# STM32G431C6T6.net
KiCad netlist of a schematic drawn in Altium Designer
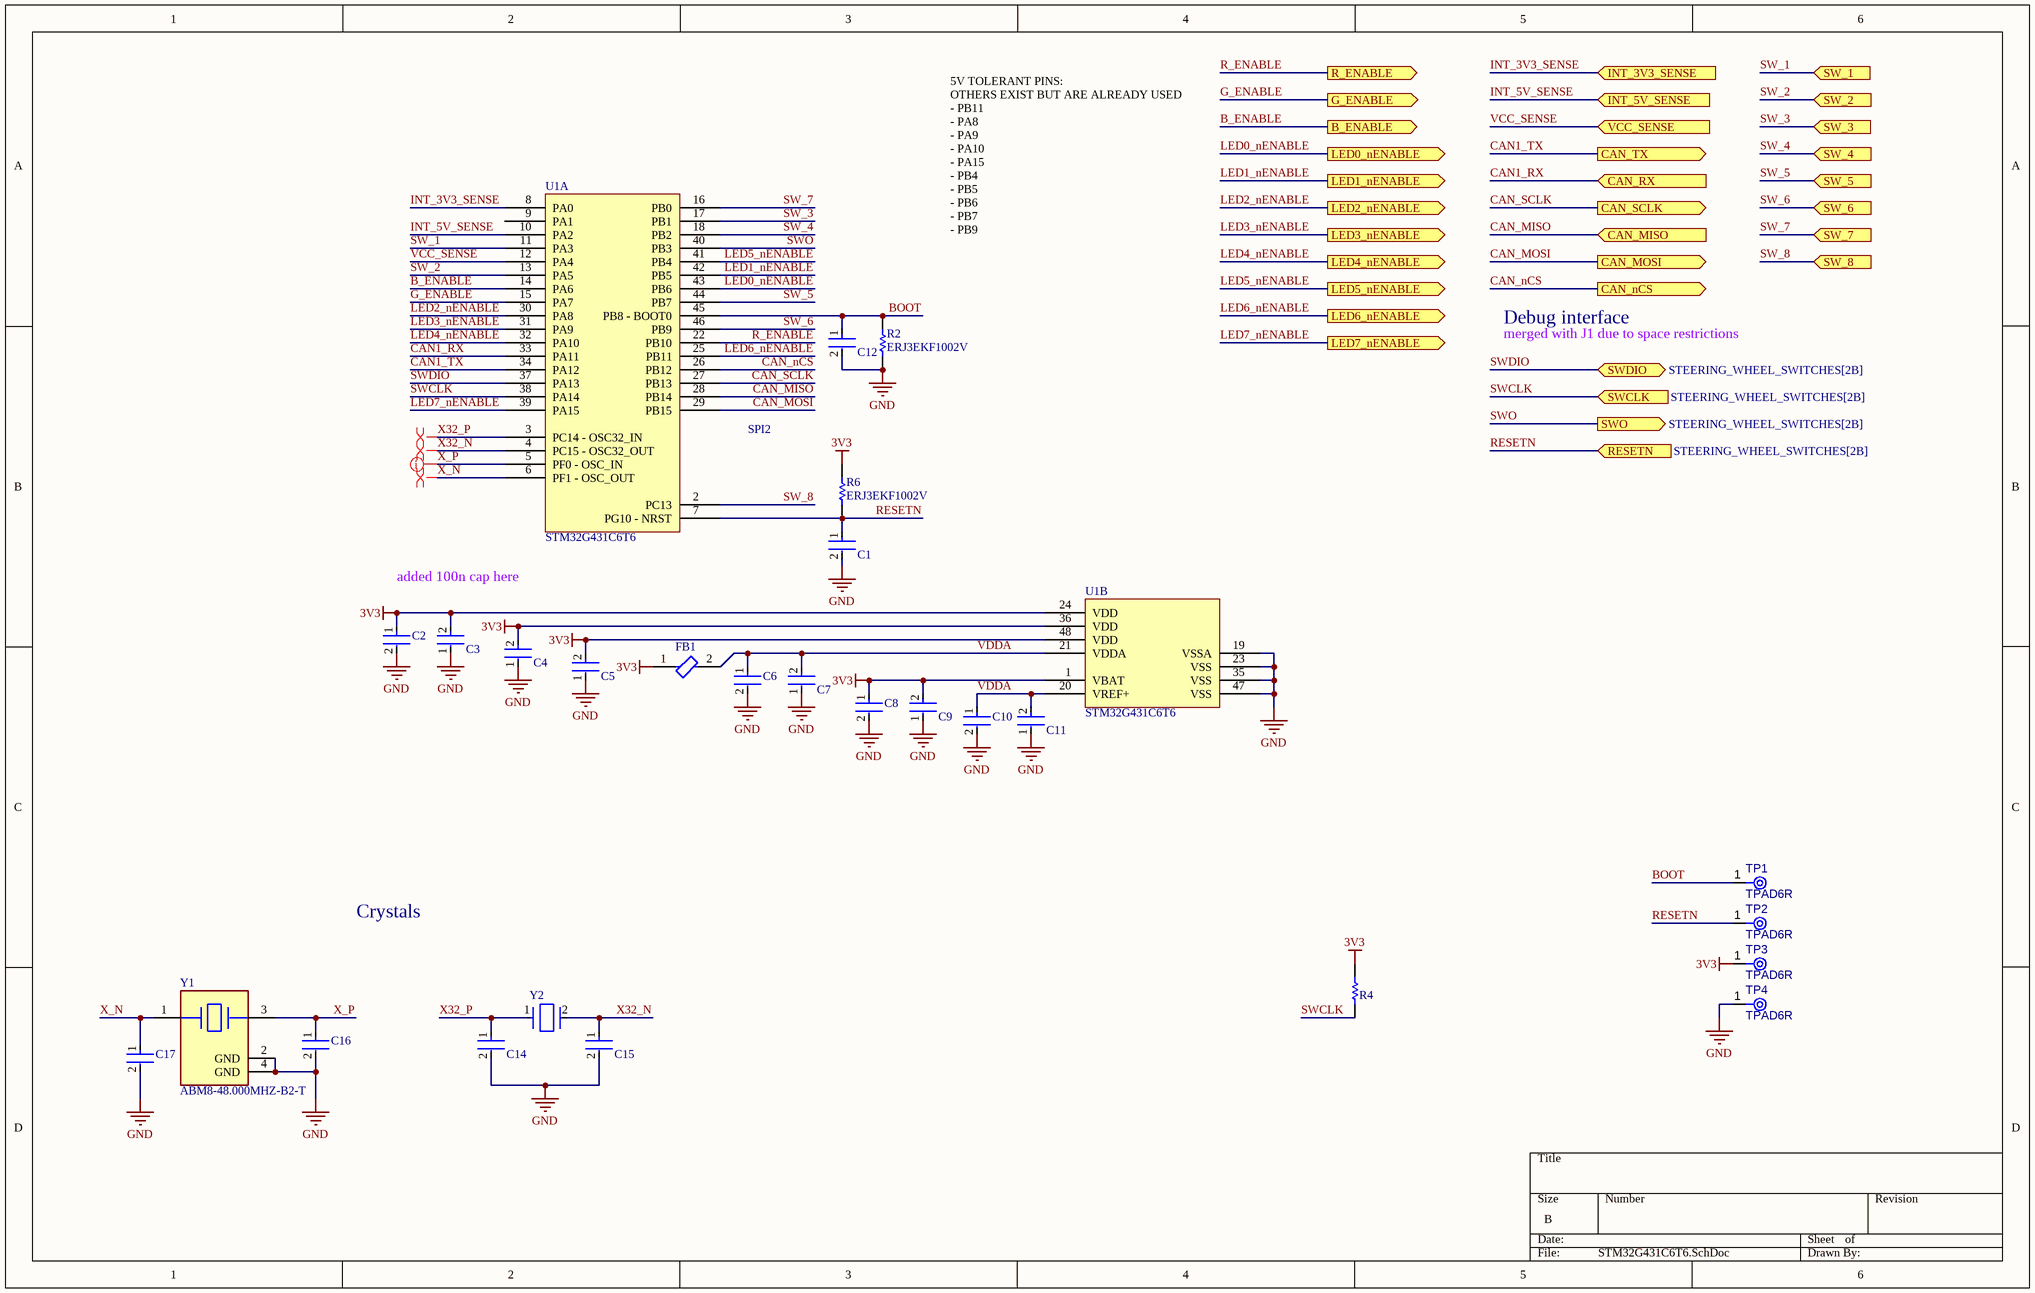
[diagram p0: STM32G431C6T6.SchDoc]

(export (version "E")
  (design (tool "Eeschema 10.0.6"))
  (components
    (comp (ref "C1")
      (value "C0402C104K8PACTU")
      (footprint "FP-C0402-BB-MFG")
      (description "CAP CER 0.1UF 10V X5R 0402")
      (fields (field (name "MANUFACTURER") "Kemet") (field (name "TOLERANCE") "0.1"))
      (libsource (lib "Altium Content Vault") (part "b4654b650e69147ec39a6b967a45e02"))
    )
    (comp (ref "C2")
      (value "C1005X5R1A475K050BC")
      (footprint "FP-C1005-050-0_15-MFG")
      (description "CAP CER 4.7UF 10V X5R 0402")
      (fields (field (name "TOLERANCE") "10%"))
      (libsource (lib "Altium Content Vault") (part "b4654b650e69147ec39a6b967a45e02"))
    )
    (comp (ref "C3")
      (value "GRM155R71C104KA88D")
      (footprint "FP-GRM15-MFG")
      (description "CAP CER 0.1UF 16V X7R 0402")
      (fields
        (field (name "TOLERANCE") "10%")
        (field (name "OCTOPART") "https://octopart.com/grm155r71c104ka88d-murata-196880")
      )
      (libsource (lib "Altium Content Vault") (part "236180d848d6139a670b325ea6854c9"))
    )
    (comp (ref "C4")
      (value "GRM155R71C104KA88D")
      (footprint "FP-GRM15-MFG")
      (description "CAP CER 0.1UF 16V X7R 0402")
      (fields
        (field (name "TOLERANCE") "10%")
        (field (name "OCTOPART") "https://octopart.com/grm155r71c104ka88d-murata-196880")
      )
      (libsource (lib "Altium Content Vault") (part "236180d848d6139a670b325ea6854c9"))
    )
    (comp (ref "C5")
      (value "GRM155R71C104KA88D")
      (footprint "FP-GRM15-MFG")
      (description "CAP CER 0.1UF 16V X7R 0402")
      (fields
        (field (name "TOLERANCE") "10%")
        (field (name "OCTOPART") "https://octopart.com/grm155r71c104ka88d-murata-196880")
      )
      (libsource (lib "Altium Content Vault") (part "236180d848d6139a670b325ea6854c9"))
    )
    (comp (ref "C6")
      (value "EMK105BJ105KV-F")
      (footprint "FP-0402-L_1_0_0_05-W_0_5-IPC_A")
      (description "None")
      (fields (field (name "TOLERANCE") "10%"))
      (libsource (lib "Altium Content Vault") (part "b4654b650e69147ec39a6b967a45e02"))
    )
    (comp (ref "C7")
      (value "GRM155R71C104KA88D")
      (footprint "FP-GRM15-MFG")
      (description "CAP CER 0.1UF 16V X7R 0402")
      (fields
        (field (name "TOLERANCE") "10%")
        (field (name "OCTOPART") "https://octopart.com/grm155r71c104ka88d-murata-196880")
      )
      (libsource (lib "Altium Content Vault") (part "236180d848d6139a670b325ea6854c9"))
    )
    (comp (ref "C8")
      (value "EMK105BJ105KV-F")
      (footprint "FP-0402-L_1_0_0_05-W_0_5-IPC_A")
      (description "None")
      (fields (field (name "TOLERANCE") "10%"))
      (libsource (lib "Altium Content Vault") (part "b4654b650e69147ec39a6b967a45e02"))
    )
    (comp (ref "C9")
      (value "GRM155R71C104KA88D")
      (footprint "FP-GRM15-MFG")
      (description "CAP CER 0.1UF 16V X7R 0402")
      (fields
        (field (name "TOLERANCE") "10%")
        (field (name "OCTOPART") "https://octopart.com/grm155r71c104ka88d-murata-196880")
      )
      (libsource (lib "Altium Content Vault") (part "236180d848d6139a670b325ea6854c9"))
    )
    (comp (ref "C10")
      (value "EMK105BJ105KV-F")
      (footprint "FP-0402-L_1_0_0_05-W_0_5-IPC_A")
      (description "None")
      (fields (field (name "TOLERANCE") "10%"))
      (libsource (lib "Altium Content Vault") (part "b4654b650e69147ec39a6b967a45e02"))
    )
    (comp (ref "C11")
      (value "GRM155R71C104KA88D")
      (footprint "FP-GRM15-MFG")
      (description "CAP CER 0.1UF 16V X7R 0402")
      (fields
        (field (name "TOLERANCE") "10%")
        (field (name "OCTOPART") "https://octopart.com/grm155r71c104ka88d-murata-196880")
      )
      (libsource (lib "Altium Content Vault") (part "236180d848d6139a670b325ea6854c9"))
    )
    (comp (ref "C12")
      (value "C0402C104K8PACTU")
      (footprint "FP-C0402-BB-MFG")
      (description "CAP CER 0.1UF 10V X5R 0402")
      (fields (field (name "MANUFACTURER") "Kemet") (field (name "TOLERANCE") "0.1"))
      (libsource (lib "Altium Content Vault") (part "b4654b650e69147ec39a6b967a45e02"))
    )
    (comp (ref "C14")
      (value "04025A180FAT2A")
      (footprint "FP-0402-L_1_0_1-W_0_5_0_1-IPC_A")
      (description "General Purpose Ceramic Capacitor, 0402, 18pF, 1%, C0G, 30ppm/°C, 50V")
      (fields (field (name "TOLERANCE") "1%"))
      (libsource (lib "Altium Content Vault") (part "b4654b650e69147ec39a6b967a45e02"))
    )
    (comp (ref "C15")
      (value "04025A180FAT2A")
      (footprint "FP-0402-L_1_0_1-W_0_5_0_1-IPC_A")
      (description "General Purpose Ceramic Capacitor, 0402, 18pF, 1%, C0G, 30ppm/°C, 50V")
      (fields (field (name "TOLERANCE") "1%"))
      (libsource (lib "Altium Content Vault") (part "b4654b650e69147ec39a6b967a45e02"))
    )
    (comp (ref "C16")
      (value "C0402C689C5GACTU")
      (footprint "FP-C0402-BB-MFG")
      (description "CAP CER 6.8PF 50V NP0 0402")
      (fields
        (field (name "OCTOPART") "https://octopart.com/c0402c689c5gactu-kemet-9143567")
        (field (name "MANUFACTURER") "Kemet")
      )
      (libsource (lib "Altium Content Vault") (part "b4654b650e69147ec39a6b967a45e02"))
    )
    (comp (ref "C17")
      (value "C0402C689C5GACTU")
      (footprint "FP-C0402-BB-MFG")
      (description "CAP CER 6.8PF 50V NP0 0402")
      (fields
        (field (name "OCTOPART") "https://octopart.com/c0402c689c5gactu-kemet-9143567")
        (field (name "MANUFACTURER") "Kemet")
      )
      (libsource (lib "Altium Content Vault") (part "b4654b650e69147ec39a6b967a45e02"))
    )
    (comp (ref "FB1")
      (value "BLM15PX601SN1D")
      (footprint "FP-BLM15-0_05-MFG")
      (description "Chip Ferrite Bead, 0402, 600Ω @ 100MHz, 0.23Ω, 25%, 900mA")
      (fields (field (name "TOLERANCE") "25%"))
      (libsource (lib "Altium Content Vault") (part "5f30dd21d616792df468990f7003faa"))
    )
    (comp (ref "R2")
      (value "ERJ3EKF1002V")
      (footprint "RESC1609X55X30LL15T15")
      (description "Chip Resistor, 10 KOhm, +/- 1%, 0.1 W, -55 to 155 degC, 0603 (1608 Metric), RoHS, Tape and Reel")
      (fields (field (name "TOLERANCE") "1%") (field (name "MANUFACTURER") "Panasonic"))
      (libsource (lib "Altium Content Vault") (part "RES-2"))
    )
    (comp (ref "R4")
      (value "ERJ3EKF1002V")
      (footprint "RESC1609X55X30LL15T15")
      (description "Chip Resistor, 10 KOhm, +/- 1%, 0.1 W, -55 to 155 degC, 0603 (1608 Metric), RoHS, Tape and Reel")
      (fields (field (name "TOLERANCE") "1%") (field (name "MANUFACTURER") "Panasonic"))
      (libsource (lib "Altium Content Vault") (part "RES-2"))
    )
    (comp (ref "R6")
      (value "ERJ3EKF1002V")
      (footprint "RESC1609X55X30LL15T15")
      (description "Chip Resistor, 10 KOhm, +/- 1%, 0.1 W, -55 to 155 degC, 0603 (1608 Metric), RoHS, Tape and Reel")
      (fields (field (name "TOLERANCE") "1%") (field (name "MANUFACTURER") "Panasonic"))
      (libsource (lib "Altium Content Vault") (part "RES-2"))
    )
    (comp (ref "TP1")
      (value "TPAD6R")
      (footprint "TP06R")
      (description "0.6mm round")
      (libsource (lib "uORocketry Hardware") (part "CMP-001-0001-4"))
    )
    (comp (ref "TP2")
      (value "TPAD6R")
      (footprint "TP06R")
      (description "0.6mm round")
      (libsource (lib "uORocketry Hardware") (part "CMP-001-0001-4"))
    )
    (comp (ref "TP3")
      (value "TPAD6R")
      (footprint "TP06R")
      (description "0.6mm round")
      (libsource (lib "uORocketry Hardware") (part "CMP-001-0001-4"))
    )
    (comp (ref "TP4")
      (value "TPAD6R")
      (footprint "TP06R")
      (description "0.6mm round")
      (libsource (lib "uORocketry Hardware") (part "CMP-001-0001-4"))
    )
    (comp (ref "U1")
      (value "STM32G431C6T6")
      (footprint "TSQFP50P900X900X160-48N")
      (description "IC MCU 32BIT 32KB FLASH 48LQFP")
      (libsource (lib "Space Concordia") (part "STM32G431C6T6"))
    )
    (comp (ref "Y1")
      (value "ABM8-48.000MHZ-B2-T")
      (footprint "FP-ABM8-MFG")
      (description "Crystal 48MHz ±20ppm 18pF SMD-4 3.2mm x 2.5mm")
      (fields (field (name "TOLERANCE") "20ppm"))
      (libsource (lib "Altium Content Vault") (part "dfdb7f9a12507849fb681da9a70121c"))
    )
    (comp (ref "Y2")
      (value "ECS-.327-12.5-1210-TR")
      (footprint "FP-ECX-1210-MFG")
      (description "CRYSTAL 32.7680KHZ 12.5PF SMD")
      (fields
        (field (name "OCTOPART") "https://octopart.com/ecs-.327-12.5-1210-tr-ecs+international-81221340")
        (field (name "TOLERANCE") "20ppm")
      )
      (libsource (lib "Altium Content Vault") (part "99724985039315a44fd0d1401b84e49"))
    )
  )
  (nets
    (net (code "1") (name "/BOOT") (class "Default")
      (node (ref "C12") (pin "1") (pinfunction "1_1") (pintype "passive"))
      (node (ref "R2") (pin "2") (pinfunction "2_2") (pintype "passive"))
      (node (ref "TP1") (pin "1") (pinfunction "TP_1") (pintype "passive"))
      (node (ref "U1") (pin "45") (pinfunction "PB8_-_BOOT0_45") (pintype "passive"))
    )
    (net (code "2") (name "/B_ENABLE") (class "Default")
      (node (ref "U1") (pin "14") (pinfunction "PA6_14") (pintype "passive"))
    )
    (net (code "3") (name "/CAN1_RX") (class "Default")
      (node (ref "U1") (pin "33") (pinfunction "PA11_33") (pintype "passive"))
    )
    (net (code "4") (name "/CAN1_TX") (class "Default")
      (node (ref "U1") (pin "34") (pinfunction "PA12_34") (pintype "passive"))
    )
    (net (code "5") (name "/CAN_MISO") (class "Default")
      (node (ref "U1") (pin "28") (pinfunction "PB14_28") (pintype "passive"))
    )
    (net (code "6") (name "/CAN_MOSI") (class "Default")
      (node (ref "U1") (pin "29") (pinfunction "PB15_29") (pintype "passive"))
    )
    (net (code "7") (name "/CAN_SCLK") (class "Default")
      (node (ref "U1") (pin "27") (pinfunction "PB13_27") (pintype "passive"))
    )
    (net (code "8") (name "/CAN_nCS") (class "Default")
      (node (ref "U1") (pin "26") (pinfunction "PB12_26") (pintype "passive"))
    )
    (net (code "9") (name "/G_ENABLE") (class "Default")
      (node (ref "U1") (pin "15") (pinfunction "PA7_15") (pintype "passive"))
    )
    (net (code "10") (name "/INT_3V3_SENSE") (class "Default")
      (node (ref "U1") (pin "8") (pinfunction "PA0_8") (pintype "passive"))
    )
    (net (code "11") (name "/INT_5V_SENSE") (class "Default")
      (node (ref "U1") (pin "10") (pinfunction "PA2_10") (pintype "passive"))
    )
    (net (code "12") (name "/LED0_nENABLE") (class "Default")
      (node (ref "U1") (pin "43") (pinfunction "PB6_43") (pintype "passive"))
    )
    (net (code "13") (name "/LED1_nENABLE") (class "Default")
      (node (ref "U1") (pin "42") (pinfunction "PB5_42") (pintype "passive"))
    )
    (net (code "14") (name "/LED2_nENABLE") (class "Default")
      (node (ref "U1") (pin "30") (pinfunction "PA8_30") (pintype "passive"))
    )
    (net (code "15") (name "/LED3_nENABLE") (class "Default")
      (node (ref "U1") (pin "31") (pinfunction "PA9_31") (pintype "passive"))
    )
    (net (code "16") (name "/LED4_nENABLE") (class "Default")
      (node (ref "U1") (pin "32") (pinfunction "PA10_32") (pintype "passive"))
    )
    (net (code "17") (name "/LED5_nENABLE") (class "Default")
      (node (ref "U1") (pin "41") (pinfunction "PB4_41") (pintype "passive"))
    )
    (net (code "18") (name "/LED6_nENABLE") (class "Default")
      (node (ref "U1") (pin "25") (pinfunction "PB11_25") (pintype "passive"))
    )
    (net (code "19") (name "/LED7_nENABLE") (class "Default")
      (node (ref "U1") (pin "39") (pinfunction "PA15_39") (pintype "passive"))
    )
    (net (code "20") (name "/RESETN") (class "Default")
      (node (ref "C1") (pin "1") (pinfunction "1_1") (pintype "passive"))
      (node (ref "R6") (pin "2") (pinfunction "2_2") (pintype "passive"))
      (node (ref "TP2") (pin "1") (pinfunction "TP_1") (pintype "passive"))
      (node (ref "U1") (pin "7") (pinfunction "PG10_-_NRST_7") (pintype "passive"))
    )
    (net (code "21") (name "/R_ENABLE") (class "Default")
      (node (ref "U1") (pin "22") (pinfunction "PB10_22") (pintype "passive"))
    )
    (net (code "22") (name "/SWCLK") (class "Default")
      (node (ref "R4") (pin "2") (pinfunction "2_2") (pintype "passive"))
      (node (ref "U1") (pin "38") (pinfunction "PA14_38") (pintype "passive"))
    )
    (net (code "23") (name "/SWDIO") (class "Default")
      (node (ref "U1") (pin "37") (pinfunction "PA13_37") (pintype "passive"))
    )
    (net (code "24") (name "/SWO") (class "Default")
      (node (ref "U1") (pin "40") (pinfunction "PB3_40") (pintype "passive"))
    )
    (net (code "25") (name "/SW_1") (class "Default")
      (node (ref "U1") (pin "11") (pinfunction "PA3_11") (pintype "passive"))
    )
    (net (code "26") (name "/SW_2") (class "Default")
      (node (ref "U1") (pin "13") (pinfunction "PA5_13") (pintype "passive"))
    )
    (net (code "27") (name "/SW_3") (class "Default")
      (node (ref "U1") (pin "17") (pinfunction "PB1_17") (pintype "passive"))
    )
    (net (code "28") (name "/SW_4") (class "Default")
      (node (ref "U1") (pin "18") (pinfunction "PB2_18") (pintype "passive"))
    )
    (net (code "29") (name "/SW_5") (class "Default")
      (node (ref "U1") (pin "44") (pinfunction "PB7_44") (pintype "passive"))
    )
    (net (code "30") (name "/SW_6") (class "Default")
      (node (ref "U1") (pin "46") (pinfunction "PB9_46") (pintype "passive"))
    )
    (net (code "31") (name "/SW_7") (class "Default")
      (node (ref "U1") (pin "16") (pinfunction "PB0_16") (pintype "passive"))
    )
    (net (code "32") (name "/SW_8") (class "Default")
      (node (ref "U1") (pin "2") (pinfunction "PC13_2") (pintype "passive"))
    )
    (net (code "33") (name "/VCC_SENSE") (class "Default")
      (node (ref "U1") (pin "12") (pinfunction "PA4_12") (pintype "passive"))
    )
    (net (code "34") (name "/VDDA") (class "Default")
      (node (ref "C10") (pin "1") (pinfunction "1_1") (pintype "passive"))
      (node (ref "C11") (pin "2") (pinfunction "2_2") (pintype "passive"))
      (node (ref "C6") (pin "1") (pinfunction "1_1") (pintype "passive"))
      (node (ref "C7") (pin "2") (pinfunction "2_2") (pintype "passive"))
      (node (ref "FB1") (pin "2") (pinfunction "2_2") (pintype "passive"))
      (node (ref "U1") (pin "20") (pinfunction "VREF+_20") (pintype "power_in"))
      (node (ref "U1") (pin "21") (pinfunction "VDDA_21") (pintype "power_in"))
    )
    (net (code "35") (name "/X32_N") (class "Default")
      (node (ref "C15") (pin "1") (pinfunction "1_1") (pintype "passive"))
      (node (ref "U1") (pin "4") (pinfunction "PC15_-_OSC32_OUT_4") (pintype "passive"))
      (node (ref "Y2") (pin "2") (pinfunction "Out/In_2") (pintype "passive"))
    )
    (net (code "36") (name "/X32_P") (class "Default")
      (node (ref "C14") (pin "1") (pinfunction "1_1") (pintype "passive"))
      (node (ref "U1") (pin "3") (pinfunction "PC14_-_OSC32_IN_3") (pintype "passive"))
      (node (ref "Y2") (pin "1") (pinfunction "In/Out_1") (pintype "passive"))
    )
    (net (code "37") (name "/X_N") (class "Default")
      (node (ref "C17") (pin "1") (pinfunction "1_1") (pintype "passive"))
      (node (ref "U1") (pin "6") (pinfunction "PF1_-_OSC_OUT_6") (pintype "passive"))
      (node (ref "Y1") (pin "1") (pinfunction "1_1") (pintype "passive"))
    )
    (net (code "38") (name "/X_P") (class "Default")
      (node (ref "C16") (pin "1") (pinfunction "1_1") (pintype "passive"))
      (node (ref "U1") (pin "5") (pinfunction "PF0_-_OSC_IN_5") (pintype "passive"))
      (node (ref "Y1") (pin "3") (pinfunction "3_3") (pintype "passive"))
    )
    (net (code "39") (name "3V3") (class "Default")
      (node (ref "C2") (pin "1") (pinfunction "1_1") (pintype "passive"))
      (node (ref "C3") (pin "2") (pinfunction "2_2") (pintype "passive"))
      (node (ref "C4") (pin "2") (pinfunction "2_2") (pintype "passive"))
      (node (ref "C5") (pin "2") (pinfunction "2_2") (pintype "passive"))
      (node (ref "C8") (pin "1") (pinfunction "1_1") (pintype "passive"))
      (node (ref "C9") (pin "2") (pinfunction "2_2") (pintype "passive"))
      (node (ref "FB1") (pin "1") (pinfunction "1_1") (pintype "passive"))
      (node (ref "R4") (pin "1") (pinfunction "1_1") (pintype "passive"))
      (node (ref "R6") (pin "1") (pinfunction "1_1") (pintype "passive"))
      (node (ref "TP3") (pin "1") (pinfunction "TP_1") (pintype "passive"))
      (node (ref "U1") (pin "1") (pinfunction "VBAT_1") (pintype "power_in"))
      (node (ref "U1") (pin "24") (pinfunction "VDD_24") (pintype "power_in"))
      (node (ref "U1") (pin "36") (pinfunction "VDD_36") (pintype "power_in"))
      (node (ref "U1") (pin "48") (pinfunction "VDD_48") (pintype "power_in"))
    )
    (net (code "40") (name "GND") (class "Default")
      (node (ref "C1") (pin "2") (pinfunction "2_2") (pintype "passive"))
      (node (ref "C10") (pin "2") (pinfunction "2_2") (pintype "passive"))
      (node (ref "C11") (pin "1") (pinfunction "1_1") (pintype "passive"))
      (node (ref "C12") (pin "2") (pinfunction "2_2") (pintype "passive"))
      (node (ref "C14") (pin "2") (pinfunction "2_2") (pintype "passive"))
      (node (ref "C15") (pin "2") (pinfunction "2_2") (pintype "passive"))
      (node (ref "C16") (pin "2") (pinfunction "2_2") (pintype "passive"))
      (node (ref "C17") (pin "2") (pinfunction "2_2") (pintype "passive"))
      (node (ref "C2") (pin "2") (pinfunction "2_2") (pintype "passive"))
      (node (ref "C3") (pin "1") (pinfunction "1_1") (pintype "passive"))
      (node (ref "C4") (pin "1") (pinfunction "1_1") (pintype "passive"))
      (node (ref "C5") (pin "1") (pinfunction "1_1") (pintype "passive"))
      (node (ref "C6") (pin "2") (pinfunction "2_2") (pintype "passive"))
      (node (ref "C7") (pin "1") (pinfunction "1_1") (pintype "passive"))
      (node (ref "C8") (pin "2") (pinfunction "2_2") (pintype "passive"))
      (node (ref "C9") (pin "1") (pinfunction "1_1") (pintype "passive"))
      (node (ref "R2") (pin "1") (pinfunction "1_1") (pintype "passive"))
      (node (ref "TP4") (pin "1") (pinfunction "TP_1") (pintype "passive"))
      (node (ref "U1") (pin "19") (pinfunction "VSSA_19") (pintype "power_in"))
      (node (ref "U1") (pin "23") (pinfunction "VSS_23") (pintype "power_in"))
      (node (ref "U1") (pin "35") (pinfunction "VSS_35") (pintype "power_in"))
      (node (ref "U1") (pin "47") (pinfunction "VSS_47") (pintype "power_in"))
      (node (ref "Y1") (pin "2") (pinfunction "GND_2") (pintype "power_in"))
      (node (ref "Y1") (pin "4") (pinfunction "GND_4") (pintype "power_in"))
    )
    (net (code "41") (name "unconnected-(U1A-PA1-Pad9)") (class "Default")
      (node (ref "U1") (pin "9") (pinfunction "PA1_9") (pintype "passive"))
    )
  )
)
